# bus_extender.net
KiCad netlist of a schematic drawn in EAGLE
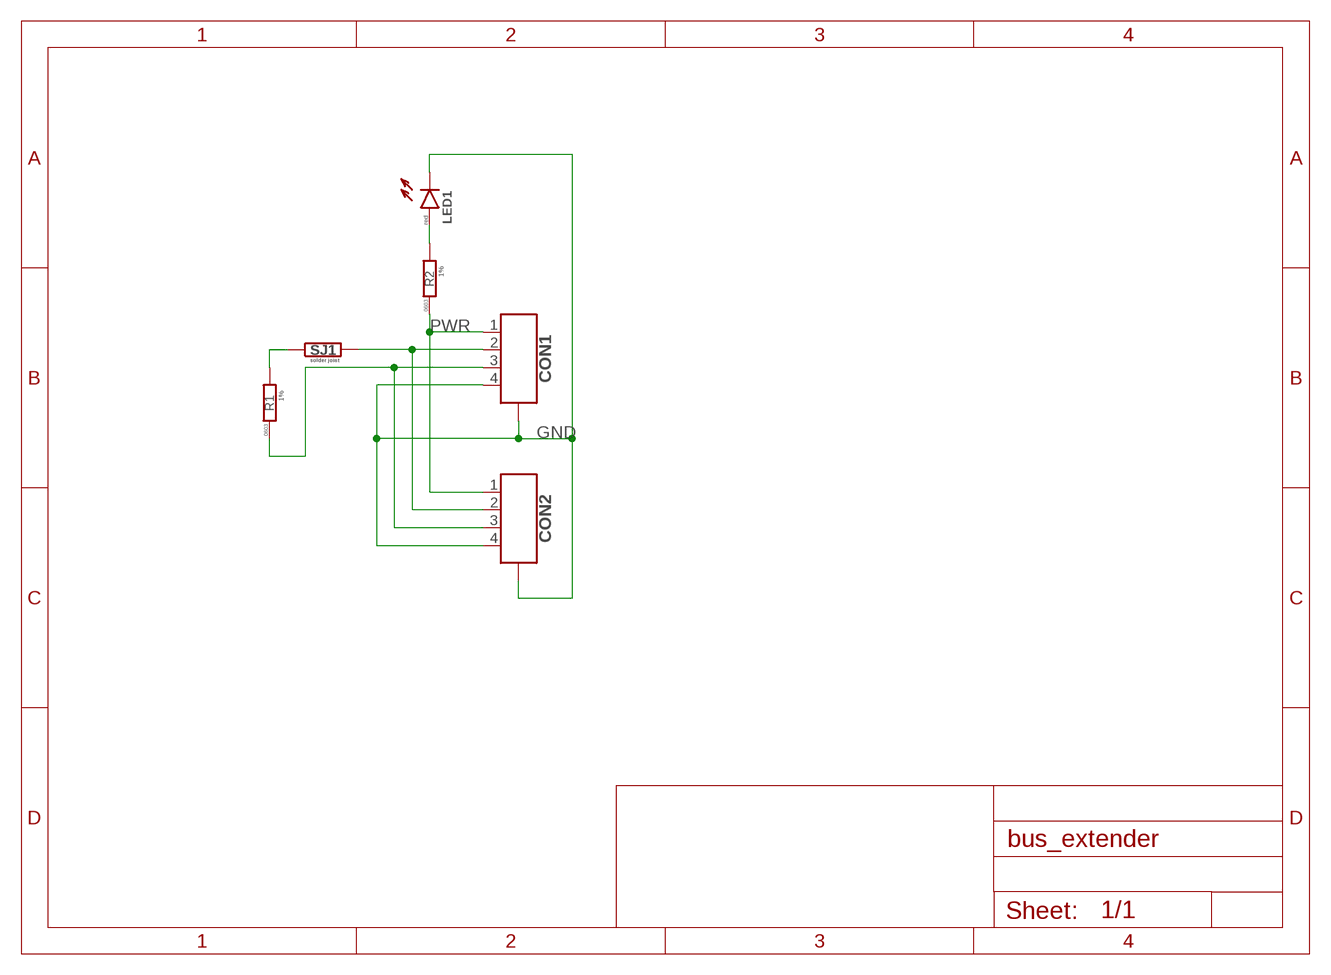
[diagram p0: schematic, sheet 1]

(export (version "E")
  (design (tool "Eeschema 10.0.6"))
  (components
    (comp (ref "CON1")
      (value "CON-4P-TABS-JST_GH-RA")
      (footprint "eagle-import:JST_GH-4P-RA")
      (fields (field (name "MANF") "JST Sales America Inc"))
      (libsource (lib "eagle-import") (part "CON-4P-TABS-RA-JST_GH"))
    )
    (comp (ref "CON2")
      (value "CON-4P-TABS-JST_GH-RA")
      (footprint "eagle-import:JST_GH-4P-RA")
      (fields (field (name "MANF") "JST Sales America Inc"))
      (libsource (lib "eagle-import") (part "CON-4P-TABS-RA-JST_GH"))
    )
    (comp (ref "LED1")
      (value "LED-0603")
      (footprint "eagle-import:LED0603")
      (fields (field (name "COLOR") "red"))
      (libsource (lib "eagle-import") (part "LED-0603"))
    )
    (comp (ref "R1")
      (value "R-1%-0603")
      (footprint "eagle-import:R0603")
      (fields (field (name "PACKAGE") "0603") (field (name "TOLERANCE") "1%"))
      (libsource (lib "eagle-import") (part "R-0603-1%"))
    )
    (comp (ref "R2")
      (value "R-1%-0603")
      (footprint "eagle-import:R0603")
      (fields (field (name "PACKAGE") "0603") (field (name "TOLERANCE") "1%"))
      (libsource (lib "eagle-import") (part "R-0603-1%"))
    )
    (comp (ref "SJ1")
      (value "SOLDER_JOINT")
      (footprint "eagle-import:RES_0")
      (libsource (lib "eagle-import") (part "SOLDER_JOINT"))
    )
  )
  (nets
    (net (code "1") (name "/GND") (class "Default")
      (node (ref "CON1") (pin "4") (pinfunction "4_4") (pintype "bidirectional"))
      (node (ref "CON1") (pin "M$0") (pinfunction "GND_M$0") (pintype "bidirectional"))
      (node (ref "CON1") (pin "M$1") (pinfunction "GND_M$1") (pintype "bidirectional"))
      (node (ref "CON2") (pin "4") (pinfunction "4_4") (pintype "bidirectional"))
      (node (ref "CON2") (pin "M$0") (pinfunction "GND_M$0") (pintype "bidirectional"))
      (node (ref "CON2") (pin "M$1") (pinfunction "GND_M$1") (pintype "bidirectional"))
      (node (ref "LED1") (pin "C") (pinfunction "C_C") (pintype "bidirectional"))
    )
    (net (code "2") (name "/PWR") (class "Default")
      (node (ref "CON1") (pin "1") (pinfunction "1_1") (pintype "bidirectional"))
      (node (ref "CON2") (pin "1") (pinfunction "1_1") (pintype "bidirectional"))
      (node (ref "R2") (pin "1") (pinfunction "1_1") (pintype "passive"))
    )
    (net (code "3") (name "Net-(CON1-Pad2)") (class "Default")
      (node (ref "CON1") (pin "2") (pinfunction "2_2") (pintype "bidirectional"))
      (node (ref "CON2") (pin "2") (pinfunction "2_2") (pintype "bidirectional"))
      (node (ref "SJ1") (pin "2") (pinfunction "2_2") (pintype "passive"))
    )
    (net (code "4") (name "Net-(CON1-Pad3)") (class "Default")
      (node (ref "CON1") (pin "3") (pinfunction "3_3") (pintype "bidirectional"))
      (node (ref "CON2") (pin "3") (pinfunction "3_3") (pintype "bidirectional"))
      (node (ref "R1") (pin "1") (pinfunction "1_1") (pintype "passive"))
    )
    (net (code "5") (name "Net-(LED1-PadA)") (class "Default")
      (node (ref "LED1") (pin "A") (pinfunction "A_A") (pintype "bidirectional"))
      (node (ref "R2") (pin "2") (pinfunction "2_2") (pintype "passive"))
    )
    (net (code "6") (name "Net-(R1-Pad2)") (class "Default")
      (node (ref "R1") (pin "2") (pinfunction "2_2") (pintype "passive"))
      (node (ref "SJ1") (pin "1") (pinfunction "1_1") (pintype "passive"))
    )
  )
)
